# RoomIndicator_Outside.net
KiCad netlist of a schematic drawn in EAGLE
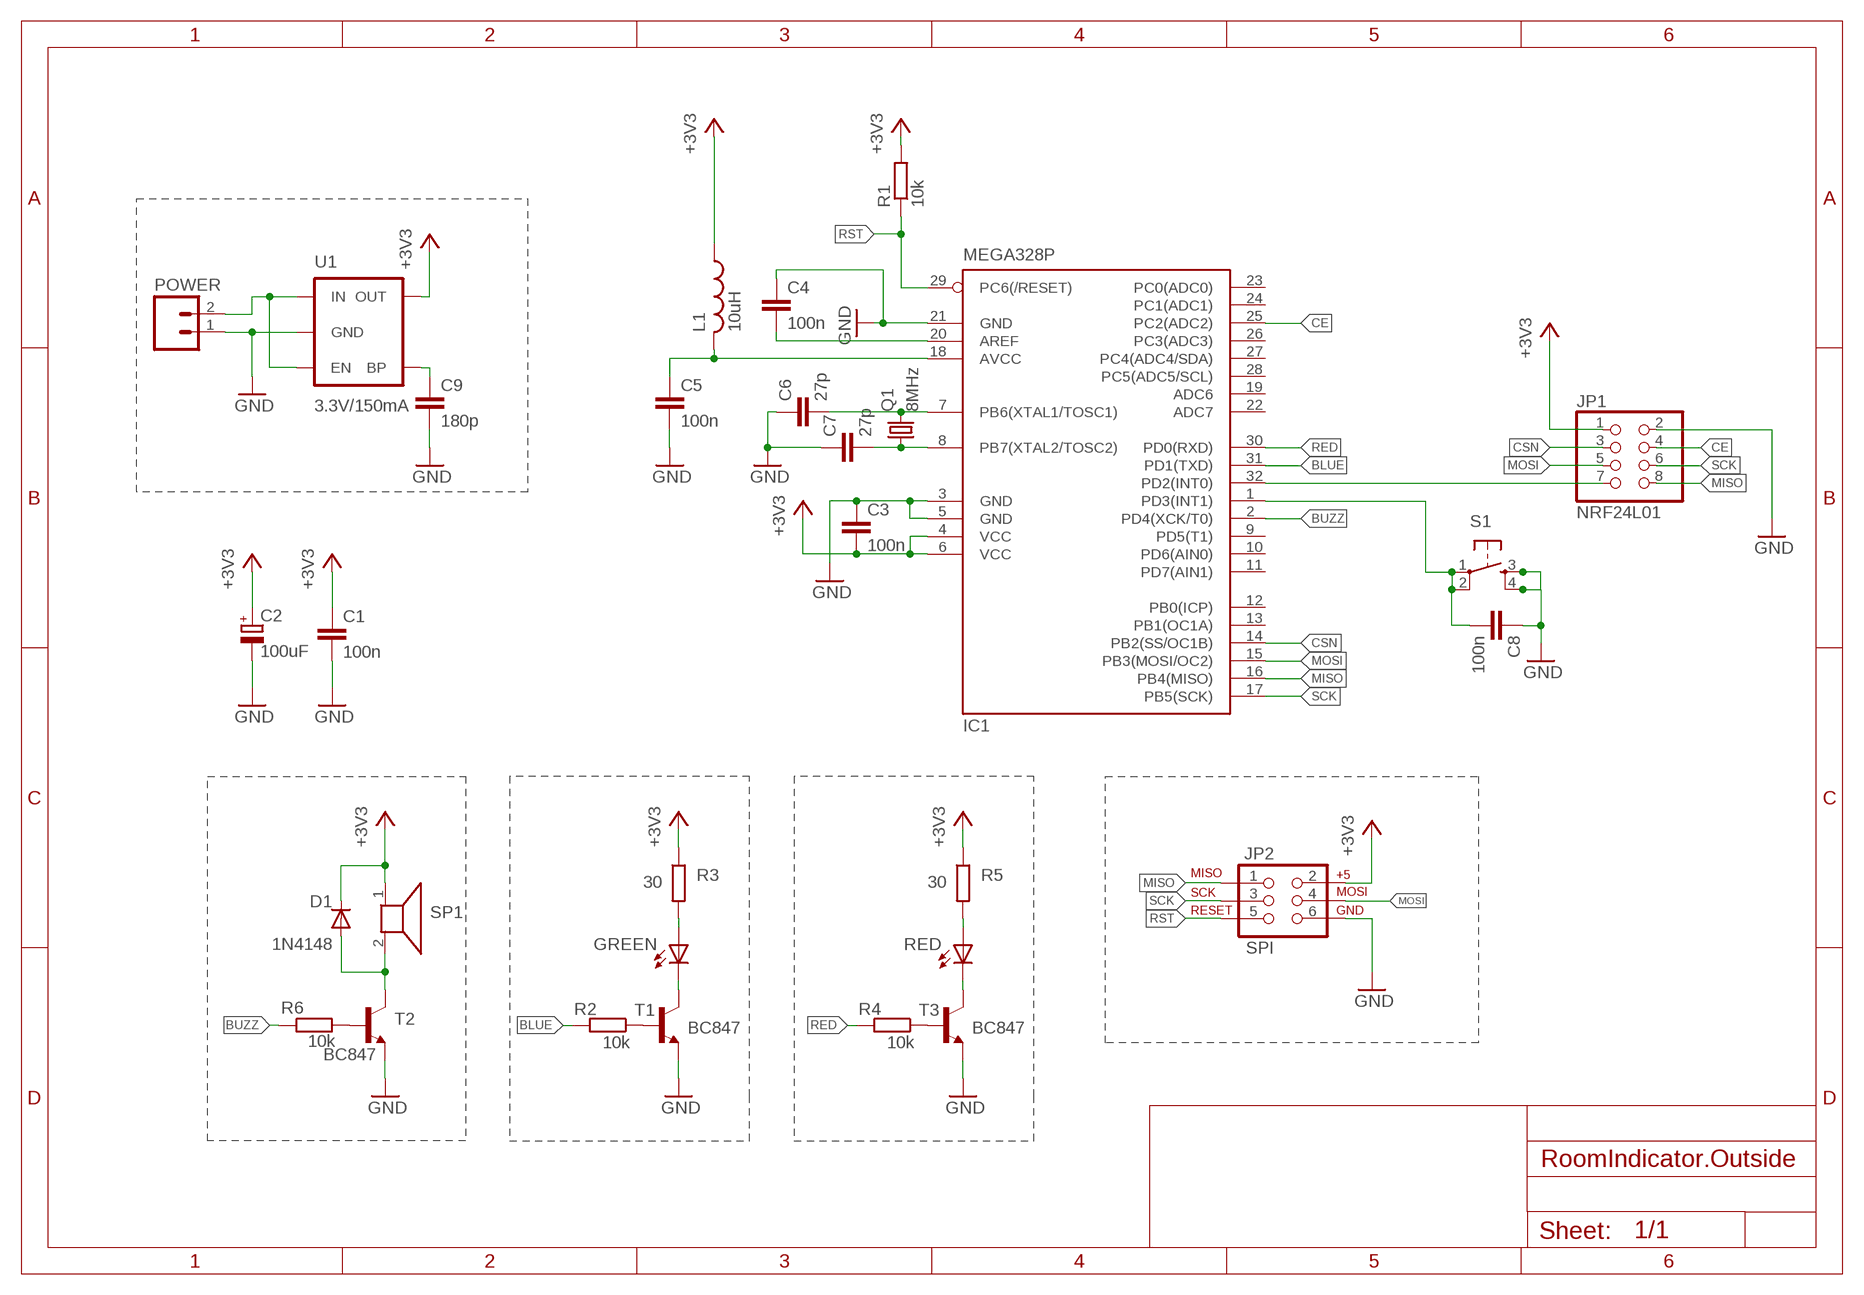
[diagram p0: schematic, sheet 1]

(export (version "E")
  (design (tool "Eeschema 10.0.6"))
  (components
    (comp (ref "C1")
      (value "100n")
      (footprint "eagle-import:C025-025X050")
      (libsource (lib "eagle-import") (part "C-EU025-025X050"))
    )
    (comp (ref "C2")
      (value "100uF")
      (footprint "eagle-import:E2,5-5")
      (libsource (lib "eagle-import") (part "CPOL-EUE2.5-5"))
    )
    (comp (ref "C3")
      (value "100n")
      (footprint "eagle-import:C0805K")
      (libsource (lib "eagle-import") (part "C-EUC0805K"))
    )
    (comp (ref "C4")
      (value "100n")
      (footprint "eagle-import:C0805K")
      (libsource (lib "eagle-import") (part "C-EUC0805K"))
    )
    (comp (ref "C5")
      (value "100n")
      (footprint "eagle-import:C0805K")
      (libsource (lib "eagle-import") (part "C-EUC0805K"))
    )
    (comp (ref "C6")
      (value "27p")
      (footprint "eagle-import:C0805K")
      (libsource (lib "eagle-import") (part "C-EUC0805K"))
    )
    (comp (ref "C7")
      (value "27p")
      (footprint "eagle-import:C0805K")
      (libsource (lib "eagle-import") (part "C-EUC0805K"))
    )
    (comp (ref "C8")
      (value "100n")
      (footprint "eagle-import:C0805K")
      (libsource (lib "eagle-import") (part "C-EUC0805K"))
    )
    (comp (ref "C9")
      (value "180p")
      (footprint "eagle-import:C0805K")
      (libsource (lib "eagle-import") (part "C-EUC0805K"))
    )
    (comp (ref "D1")
      (value "1N4148")
      (footprint "eagle-import:DO35-7")
      (libsource (lib "eagle-import") (part "1N4148DO35-7"))
    )
    (comp (ref "GREEN")
      (value "GREEN")
      (footprint "eagle-import:LED5MM")
      (libsource (lib "eagle-import") (part "LED5MM"))
    )
    (comp (ref "IC1")
      (value "MEGA328P")
      (footprint "eagle-import:TQFP32-08")
      (fields (field (name "MPN") "ATMEGA8-16AU"))
      (libsource (lib "eagle-import") (part "MEGA8-AI"))
    )
    (comp (ref "JP1")
      (value "NRF24L01")
      (footprint "eagle-import:2X04")
      (libsource (lib "eagle-import") (part "PINHD-2X4"))
    )
    (comp (ref "JP2")
      (value "SPI")
      (footprint "eagle-import:2X3")
      (libsource (lib "eagle-import") (part "AVR_SPI_PRG_6PTH"))
    )
    (comp (ref "L1")
      (value "10uH")
      (footprint "eagle-import:0204_7")
      (libsource (lib "eagle-import") (part "L-US0204/7"))
    )
    (comp (ref "POWER")
      (value "M02PTH")
      (footprint "eagle-import:1X02")
      (libsource (lib "eagle-import") (part "M02PTH"))
    )
    (comp (ref "Q1")
      (value "8MHz")
      (footprint "eagle-import:HC49_S")
      (libsource (lib "eagle-import") (part "CRYSTALHC49S"))
    )
    (comp (ref "R1")
      (value "10k")
      (footprint "eagle-import:R0805")
      (libsource (lib "eagle-import") (part "R-EU_R0805"))
    )
    (comp (ref "R2")
      (value "10k")
      (footprint "eagle-import:R0805")
      (libsource (lib "eagle-import") (part "R-EU_R0805"))
    )
    (comp (ref "R3")
      (value "30")
      (footprint "eagle-import:0204_5")
      (libsource (lib "eagle-import") (part "R-EU_0204/5"))
    )
    (comp (ref "R4")
      (value "10k")
      (footprint "eagle-import:R0805")
      (libsource (lib "eagle-import") (part "R-EU_R0805"))
    )
    (comp (ref "R5")
      (value "30")
      (footprint "eagle-import:0204_5")
      (libsource (lib "eagle-import") (part "R-EU_0204/5"))
    )
    (comp (ref "R6")
      (value "10k")
      (footprint "eagle-import:R0805")
      (libsource (lib "eagle-import") (part "R-EU_R0805"))
    )
    (comp (ref "RED")
      (value "GREEN")
      (footprint "eagle-import:LED5MM")
      (libsource (lib "eagle-import") (part "LED5MM"))
    )
    (comp (ref "S1")
      (value "TAC_SWITCHPTH")
      (footprint "eagle-import:TACTILE-PTH")
      (libsource (lib "eagle-import") (part "TAC_SWITCHPTH"))
    )
    (comp (ref "SP1")
      (value "AL60PWIDE")
      (footprint "eagle-import:AL80P")
      (libsource (lib "eagle-import") (part "AL60PWIDE"))
    )
    (comp (ref "T1")
      (value "BC847")
      (footprint "eagle-import:SOT23")
      (libsource (lib "eagle-import") (part "BC847"))
    )
    (comp (ref "T2")
      (value "BC847")
      (footprint "eagle-import:SOT23")
      (libsource (lib "eagle-import") (part "BC847"))
    )
    (comp (ref "T3")
      (value "BC847")
      (footprint "eagle-import:SOT23")
      (libsource (lib "eagle-import") (part "BC847"))
    )
    (comp (ref "U1")
      (value "3.3V/150mA")
      (footprint "eagle-import:SOT23-5")
      (libsource (lib "eagle-import") (part "V_REG_MIC52053.3V"))
    )
  )
  (nets
    (net (code "1") (name "+3V3") (class "Default")
      (node (ref "C1") (pin "1") (pinfunction "1_1") (pintype "passive"))
      (node (ref "C2") (pin "+") (pinfunction "+_+") (pintype "passive"))
      (node (ref "C3") (pin "2") (pinfunction "2_2") (pintype "passive"))
      (node (ref "D1") (pin "C") (pinfunction "C_C") (pintype "passive"))
      (node (ref "IC1") (pin "4") (pinfunction "VCC_4") (pintype "power_in"))
      (node (ref "IC1") (pin "6") (pinfunction "VCC_6") (pintype "power_in"))
      (node (ref "JP1") (pin "1") (pinfunction "1_1") (pintype "passive"))
      (node (ref "JP2") (pin "2") (pinfunction "2_2") (pintype "passive"))
      (node (ref "L1") (pin "1") (pinfunction "1_1") (pintype "passive"))
      (node (ref "R1") (pin "2") (pinfunction "2_2") (pintype "passive"))
      (node (ref "R3") (pin "1") (pinfunction "1_1") (pintype "passive"))
      (node (ref "R5") (pin "1") (pinfunction "1_1") (pintype "passive"))
      (node (ref "SP1") (pin "1") (pinfunction "1_1") (pintype "passive"))
      (node (ref "U1") (pin "5") (pinfunction "OUT_5") (pintype "passive"))
    )
    (net (code "2") (name "BLUE") (class "Default")
      (node (ref "IC1") (pin "31") (pinfunction "PD1(TXD)_31") (pintype "bidirectional"))
      (node (ref "R2") (pin "2") (pinfunction "2_2") (pintype "passive"))
    )
    (net (code "3") (name "BUZZ") (class "Default")
      (node (ref "IC1") (pin "2") (pinfunction "PD4(XCK/T0)_2") (pintype "bidirectional"))
      (node (ref "R6") (pin "1") (pinfunction "1_1") (pintype "passive"))
    )
    (net (code "4") (name "CE") (class "Default")
      (node (ref "IC1") (pin "25") (pinfunction "PC2(ADC2)_25") (pintype "bidirectional"))
      (node (ref "JP1") (pin "4") (pinfunction "4_4") (pintype "passive"))
    )
    (net (code "5") (name "CSN") (class "Default")
      (node (ref "IC1") (pin "14") (pinfunction "PB2(SS/OC1B)_14") (pintype "bidirectional"))
      (node (ref "JP1") (pin "3") (pinfunction "3_3") (pintype "passive"))
    )
    (net (code "6") (name "GND") (class "Default")
      (node (ref "C1") (pin "2") (pinfunction "2_2") (pintype "passive"))
      (node (ref "C2") (pin "-") (pinfunction "-_-") (pintype "passive"))
      (node (ref "C3") (pin "1") (pinfunction "1_1") (pintype "passive"))
      (node (ref "C4") (pin "1") (pinfunction "1_1") (pintype "passive"))
      (node (ref "C5") (pin "2") (pinfunction "2_2") (pintype "passive"))
      (node (ref "C6") (pin "1") (pinfunction "1_1") (pintype "passive"))
      (node (ref "C7") (pin "1") (pinfunction "1_1") (pintype "passive"))
      (node (ref "C8") (pin "1") (pinfunction "1_1") (pintype "passive"))
      (node (ref "C9") (pin "2") (pinfunction "2_2") (pintype "passive"))
      (node (ref "IC1") (pin "21") (pinfunction "GND_21") (pintype "power_in"))
      (node (ref "IC1") (pin "3") (pinfunction "GND_3") (pintype "power_in"))
      (node (ref "IC1") (pin "5") (pinfunction "GND_5") (pintype "power_in"))
      (node (ref "JP1") (pin "2") (pinfunction "2_2") (pintype "passive"))
      (node (ref "JP2") (pin "6") (pinfunction "6_6") (pintype "passive"))
      (node (ref "POWER") (pin "1") (pinfunction "1_1") (pintype "passive"))
      (node (ref "S1") (pin "3") (pinfunction "3_3") (pintype "passive"))
      (node (ref "S1") (pin "4") (pinfunction "4_4") (pintype "passive"))
      (node (ref "T1") (pin "2") (pinfunction "E_2") (pintype "passive"))
      (node (ref "T2") (pin "2") (pinfunction "E_2") (pintype "passive"))
      (node (ref "T3") (pin "2") (pinfunction "E_2") (pintype "passive"))
      (node (ref "U1") (pin "2") (pinfunction "GND_2") (pintype "input"))
    )
    (net (code "7") (name "MISO") (class "Default")
      (node (ref "IC1") (pin "16") (pinfunction "PB4(MISO)_16") (pintype "bidirectional"))
      (node (ref "JP1") (pin "8") (pinfunction "8_8") (pintype "passive"))
      (node (ref "JP2") (pin "1") (pinfunction "1_1") (pintype "passive"))
    )
    (net (code "8") (name "MOSI") (class "Default")
      (node (ref "IC1") (pin "15") (pinfunction "PB3(MOSI/OC2)_15") (pintype "bidirectional"))
      (node (ref "JP1") (pin "5") (pinfunction "5_5") (pintype "passive"))
      (node (ref "JP2") (pin "4") (pinfunction "4_4") (pintype "passive"))
    )
    (net (code "9") (name "Net-(GREEN-C)") (class "Default")
      (node (ref "GREEN") (pin "K") (pinfunction "C_K") (pintype "passive"))
      (node (ref "T1") (pin "3") (pinfunction "C_3") (pintype "passive"))
    )
    (net (code "10") (name "Net-(GREEN-PadA)") (class "Default")
      (node (ref "GREEN") (pin "A") (pinfunction "A_A") (pintype "passive"))
      (node (ref "R3") (pin "2") (pinfunction "2_2") (pintype "passive"))
    )
    (net (code "11") (name "Net-(IC1-AREF)") (class "Default")
      (node (ref "C4") (pin "2") (pinfunction "2_2") (pintype "passive"))
      (node (ref "IC1") (pin "20") (pinfunction "AREF_20") (pintype "passive"))
    )
    (net (code "12") (name "Net-(IC1-AVCC)") (class "Default")
      (node (ref "C5") (pin "1") (pinfunction "1_1") (pintype "passive"))
      (node (ref "IC1") (pin "18") (pinfunction "AVCC_18") (pintype "power_in"))
      (node (ref "L1") (pin "2") (pinfunction "2_2") (pintype "passive"))
    )
    (net (code "13") (name "Net-(IC1-PB6(XTAL1{slash}TOSC1))") (class "Default")
      (node (ref "C6") (pin "2") (pinfunction "2_2") (pintype "passive"))
      (node (ref "IC1") (pin "7") (pinfunction "PB6(XTAL1/TOSC1)_7") (pintype "bidirectional"))
      (node (ref "Q1") (pin "2") (pinfunction "2_2") (pintype "passive"))
    )
    (net (code "14") (name "Net-(IC1-PB7(XTAL2{slash}TOSC2))") (class "Default")
      (node (ref "C7") (pin "2") (pinfunction "2_2") (pintype "passive"))
      (node (ref "IC1") (pin "8") (pinfunction "PB7(XTAL2/TOSC2)_8") (pintype "bidirectional"))
      (node (ref "Q1") (pin "1") (pinfunction "1_1") (pintype "passive"))
    )
    (net (code "15") (name "Net-(IC1-PD2(INT0))") (class "Default")
      (node (ref "IC1") (pin "32") (pinfunction "PD2(INT0)_32") (pintype "bidirectional"))
      (node (ref "JP1") (pin "7") (pinfunction "7_7") (pintype "passive"))
    )
    (net (code "16") (name "Net-(IC1-PD3(INT1))") (class "Default")
      (node (ref "C8") (pin "2") (pinfunction "2_2") (pintype "passive"))
      (node (ref "IC1") (pin "1") (pinfunction "PD3(INT1)_1") (pintype "bidirectional"))
      (node (ref "S1") (pin "1") (pinfunction "1_1") (pintype "passive"))
      (node (ref "S1") (pin "2") (pinfunction "2_2") (pintype "passive"))
    )
    (net (code "17") (name "Net-(R5-Pad2)") (class "Default")
      (node (ref "R5") (pin "2") (pinfunction "2_2") (pintype "passive"))
      (node (ref "RED") (pin "A") (pinfunction "A_A") (pintype "passive"))
    )
    (net (code "18") (name "Net-(RED-C)") (class "Default")
      (node (ref "RED") (pin "K") (pinfunction "C_K") (pintype "passive"))
      (node (ref "T3") (pin "3") (pinfunction "C_3") (pintype "passive"))
    )
    (net (code "19") (name "Net-(T1-B)") (class "Default")
      (node (ref "R2") (pin "1") (pinfunction "1_1") (pintype "passive"))
      (node (ref "T1") (pin "1") (pinfunction "B_1") (pintype "passive"))
    )
    (net (code "20") (name "Net-(T2-B)") (class "Default")
      (node (ref "R6") (pin "2") (pinfunction "2_2") (pintype "passive"))
      (node (ref "T2") (pin "1") (pinfunction "B_1") (pintype "passive"))
    )
    (net (code "21") (name "Net-(T2-C)") (class "Default")
      (node (ref "D1") (pin "A") (pinfunction "A_A") (pintype "passive"))
      (node (ref "SP1") (pin "2") (pinfunction "2_2") (pintype "passive"))
      (node (ref "T2") (pin "3") (pinfunction "C_3") (pintype "passive"))
    )
    (net (code "22") (name "Net-(T3-B)") (class "Default")
      (node (ref "R4") (pin "1") (pinfunction "1_1") (pintype "passive"))
      (node (ref "T3") (pin "1") (pinfunction "B_1") (pintype "passive"))
    )
    (net (code "23") (name "Net-(U1-BP)") (class "Default")
      (node (ref "C9") (pin "1") (pinfunction "1_1") (pintype "passive"))
      (node (ref "U1") (pin "4") (pinfunction "BP_4") (pintype "input"))
    )
    (net (code "24") (name "Net-(U1-EN)") (class "Default")
      (node (ref "POWER") (pin "2") (pinfunction "2_2") (pintype "passive"))
      (node (ref "U1") (pin "1") (pinfunction "IN_1") (pintype "input"))
      (node (ref "U1") (pin "3") (pinfunction "EN_3") (pintype "input"))
    )
    (net (code "25") (name "RED") (class "Default")
      (node (ref "IC1") (pin "30") (pinfunction "PD0(RXD)_30") (pintype "bidirectional"))
      (node (ref "R4") (pin "2") (pinfunction "2_2") (pintype "passive"))
    )
    (net (code "26") (name "RST") (class "Default")
      (node (ref "IC1") (pin "29") (pinfunction "PC6(/RESET)_29") (pintype "bidirectional"))
      (node (ref "JP2") (pin "5") (pinfunction "5_5") (pintype "passive"))
      (node (ref "R1") (pin "1") (pinfunction "1_1") (pintype "passive"))
    )
    (net (code "27") (name "SCK") (class "Default")
      (node (ref "IC1") (pin "17") (pinfunction "PB5(SCK)_17") (pintype "bidirectional"))
      (node (ref "JP1") (pin "6") (pinfunction "6_6") (pintype "passive"))
      (node (ref "JP2") (pin "3") (pinfunction "3_3") (pintype "passive"))
    )
    (net (code "28") (name "unconnected-(IC1-ADC6-Pad19)") (class "Default")
      (node (ref "IC1") (pin "19") (pinfunction "ADC6_19") (pintype "bidirectional"))
    )
    (net (code "29") (name "unconnected-(IC1-ADC7-Pad22)") (class "Default")
      (node (ref "IC1") (pin "22") (pinfunction "ADC7_22") (pintype "bidirectional"))
    )
    (net (code "30") (name "unconnected-(IC1-PB0(ICP)-Pad12)") (class "Default")
      (node (ref "IC1") (pin "12") (pinfunction "PB0(ICP)_12") (pintype "bidirectional"))
    )
    (net (code "31") (name "unconnected-(IC1-PB1(OC1A)-Pad13)") (class "Default")
      (node (ref "IC1") (pin "13") (pinfunction "PB1(OC1A)_13") (pintype "bidirectional"))
    )
    (net (code "32") (name "unconnected-(IC1-PC0(ADC0)-Pad23)") (class "Default")
      (node (ref "IC1") (pin "23") (pinfunction "PC0(ADC0)_23") (pintype "bidirectional"))
    )
    (net (code "33") (name "unconnected-(IC1-PC1(ADC1)-Pad24)") (class "Default")
      (node (ref "IC1") (pin "24") (pinfunction "PC1(ADC1)_24") (pintype "bidirectional"))
    )
    (net (code "34") (name "unconnected-(IC1-PC3(ADC3)-Pad26)") (class "Default")
      (node (ref "IC1") (pin "26") (pinfunction "PC3(ADC3)_26") (pintype "bidirectional"))
    )
    (net (code "35") (name "unconnected-(IC1-PC4(ADC4{slash}SDA)-Pad27)") (class "Default")
      (node (ref "IC1") (pin "27") (pinfunction "PC4(ADC4/SDA)_27") (pintype "bidirectional"))
    )
    (net (code "36") (name "unconnected-(IC1-PC5(ADC5{slash}SCL)-Pad28)") (class "Default")
      (node (ref "IC1") (pin "28") (pinfunction "PC5(ADC5/SCL)_28") (pintype "bidirectional"))
    )
    (net (code "37") (name "unconnected-(IC1-PD5(T1)-Pad9)") (class "Default")
      (node (ref "IC1") (pin "9") (pinfunction "PD5(T1)_9") (pintype "bidirectional"))
    )
    (net (code "38") (name "unconnected-(IC1-PD6(AIN0)-Pad10)") (class "Default")
      (node (ref "IC1") (pin "10") (pinfunction "PD6(AIN0)_10") (pintype "bidirectional"))
    )
    (net (code "39") (name "unconnected-(IC1-PD7(AIN1)-Pad11)") (class "Default")
      (node (ref "IC1") (pin "11") (pinfunction "PD7(AIN1)_11") (pintype "bidirectional"))
    )
  )
)
